# ESP12_BusinessCard.net
KiCad netlist of a schematic drawn in EAGLE
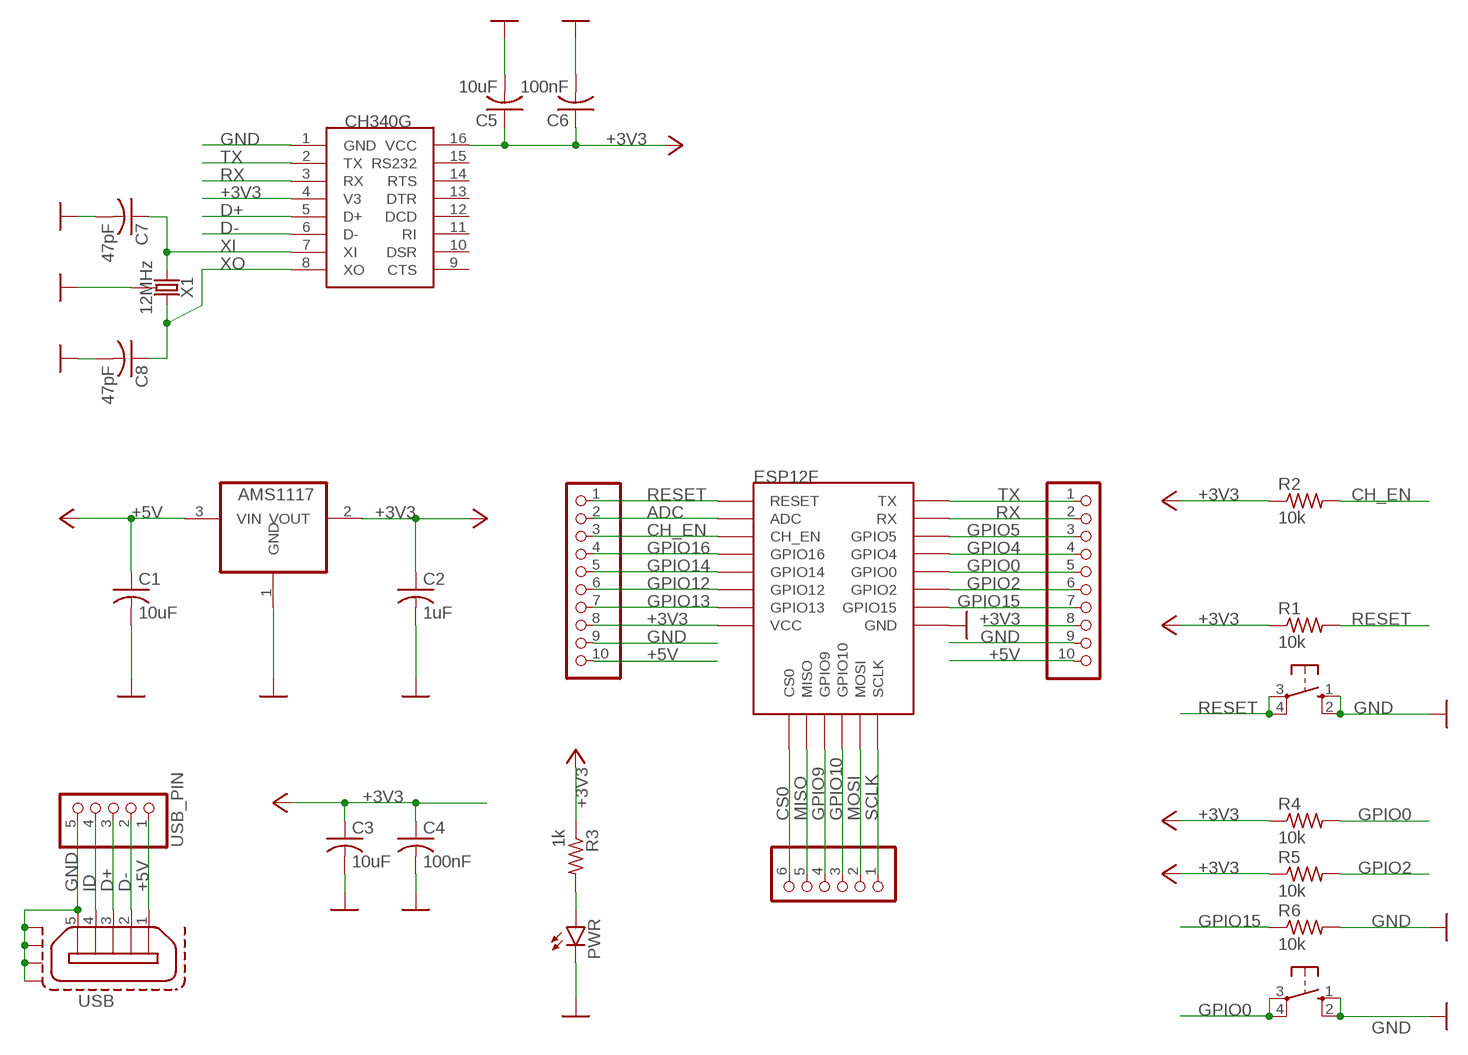
[diagram p0: schematic, sheet 1]

(export (version "E")
  (design (tool "Eeschema 10.0.6"))
  (components
    (comp (ref "AMS1117")
      (value "AMS1117")
      (footprint "eagle-import:SOT223")
      (fields (field (name "MPN") "REG1117"))
      (libsource (lib "eagle-import") (part "REG1117"))
    )
    (comp (ref "C1")
      (value "10uF")
      (footprint "eagle-import:C0805")
      (libsource (lib "eagle-import") (part "C-USC0805"))
    )
    (comp (ref "C2")
      (value "1uF")
      (footprint "eagle-import:C0805")
      (libsource (lib "eagle-import") (part "C-USC0805"))
    )
    (comp (ref "C3")
      (value "10uF")
      (footprint "eagle-import:C0805")
      (libsource (lib "eagle-import") (part "C-USC0805"))
    )
    (comp (ref "C4")
      (value "100nF")
      (footprint "eagle-import:C0805")
      (libsource (lib "eagle-import") (part "C-USC0805"))
    )
    (comp (ref "C5")
      (value "10uF")
      (footprint "eagle-import:C0805")
      (libsource (lib "eagle-import") (part "C-USC0805"))
    )
    (comp (ref "C6")
      (value "100nF")
      (footprint "eagle-import:C0805")
      (libsource (lib "eagle-import") (part "C-USC0805"))
    )
    (comp (ref "C7")
      (value "47pF")
      (footprint "eagle-import:C0805")
      (libsource (lib "eagle-import") (part "C-USC0805"))
    )
    (comp (ref "C8")
      (value "47pF")
      (footprint "eagle-import:C0805")
      (libsource (lib "eagle-import") (part "C-USC0805"))
    )
    (comp (ref "CH340G")
      (value "CH340G")
      (footprint "eagle-import:SOIC16")
      (libsource (lib "eagle-import") (part "CH340G"))
    )
    (comp (ref "ESP12F")
      (value "ESP12FSMD")
      (footprint "eagle-import:ESP12E-SMD")
      (libsource (lib "eagle-import") (part "ESP12FSMD"))
    )
    (comp (ref "JP1")
      (value "PINHD-1X10")
      (footprint "eagle-import:1X10")
      (libsource (lib "eagle-import") (part "PINHD-1X10"))
    )
    (comp (ref "JP2")
      (value "PINHD-1X10")
      (footprint "eagle-import:1X10")
      (libsource (lib "eagle-import") (part "PINHD-1X10"))
    )
    (comp (ref "JP3")
      (value "PINHD-1X6")
      (footprint "eagle-import:1X06")
      (libsource (lib "eagle-import") (part "PINHD-1X6"))
    )
    (comp (ref "PWR")
      (value "LEDCHIP-LED0603")
      (footprint "eagle-import:CHIP-LED0603")
      (libsource (lib "eagle-import") (part "LEDCHIP-LED0603"))
    )
    (comp (ref "R1")
      (value "10k")
      (footprint "eagle-import:R0805")
      (libsource (lib "eagle-import") (part "R-US_R0805"))
    )
    (comp (ref "R2")
      (value "10k")
      (footprint "eagle-import:R0805")
      (libsource (lib "eagle-import") (part "R-US_R0805"))
    )
    (comp (ref "R3")
      (value "1k")
      (footprint "eagle-import:R0805")
      (libsource (lib "eagle-import") (part "R-US_R0805"))
    )
    (comp (ref "R4")
      (value "10k")
      (footprint "eagle-import:R0805")
      (libsource (lib "eagle-import") (part "R-US_R0805"))
    )
    (comp (ref "R5")
      (value "10k")
      (footprint "eagle-import:R0805")
      (libsource (lib "eagle-import") (part "R-US_R0805"))
    )
    (comp (ref "R6")
      (value "10k")
      (footprint "eagle-import:R0805")
      (libsource (lib "eagle-import") (part "R-US_R0805"))
    )
    (comp (ref "S_PROG")
      (value "10-XX")
      (footprint "eagle-import:B3F-10XX")
      (fields (field (name "MPN") "B3F-1000"))
      (libsource (lib "eagle-import") (part "10-XX"))
    )
    (comp (ref "S_RESET")
      (value "10-XX")
      (footprint "eagle-import:B3F-10XX")
      (fields (field (name "MPN") "B3F-1000"))
      (libsource (lib "eagle-import") (part "10-XX"))
    )
    (comp (ref "USB")
      (value "ZX62D-B-5PA8")
      (footprint "eagle-import:ZX62D-B-5PA8")
      (fields (field (name "MF") "Hirose"))
      (libsource (lib "eagle-import") (part "ZX62D-B-5PA8"))
    )
    (comp (ref "USB_PIN")
      (value "PINHD-1X5")
      (footprint "eagle-import:1X05")
      (libsource (lib "eagle-import") (part "PINHD-1X5"))
    )
    (comp (ref "X1")
      (value "12MHz")
      (footprint "eagle-import:CRYSTAL-SMD-3.2X2.5MM")
      (libsource (lib "eagle-import") (part "CRYSTAL-GROUNDEDSMD-3.2X2.5"))
    )
  )
  (nets
    (net (code "1") (name "+3V3") (class "Default")
      (node (ref "AMS1117") (pin "2") (pinfunction "VOUT_2") (pintype "output"))
      (node (ref "C2") (pin "1") (pinfunction "1_1") (pintype "passive"))
      (node (ref "C3") (pin "1") (pinfunction "1_1") (pintype "passive"))
      (node (ref "C4") (pin "1") (pinfunction "1_1") (pintype "passive"))
      (node (ref "C5") (pin "1") (pinfunction "1_1") (pintype "passive"))
      (node (ref "C6") (pin "1") (pinfunction "1_1") (pintype "passive"))
      (node (ref "CH340G") (pin "16") (pinfunction "VCC_16") (pintype "bidirectional"))
      (node (ref "CH340G") (pin "4") (pinfunction "V3_4") (pintype "bidirectional"))
      (node (ref "ESP12F") (pin "VCC") (pinfunction "VCC_VCC") (pintype "bidirectional"))
      (node (ref "JP1") (pin "8") (pinfunction "8_8") (pintype "passive"))
      (node (ref "JP2") (pin "8") (pinfunction "8_8") (pintype "passive"))
      (node (ref "R1") (pin "1") (pinfunction "1_1") (pintype "passive"))
      (node (ref "R2") (pin "1") (pinfunction "1_1") (pintype "passive"))
      (node (ref "R3") (pin "1") (pinfunction "1_1") (pintype "passive"))
      (node (ref "R4") (pin "1") (pinfunction "1_1") (pintype "passive"))
      (node (ref "R5") (pin "1") (pinfunction "1_1") (pintype "passive"))
    )
    (net (code "2") (name "+5V") (class "Default")
      (node (ref "AMS1117") (pin "3") (pinfunction "VIN_3") (pintype "input"))
      (node (ref "C1") (pin "1") (pinfunction "1_1") (pintype "passive"))
      (node (ref "JP1") (pin "10") (pinfunction "10_10") (pintype "passive"))
      (node (ref "JP2") (pin "10") (pinfunction "10_10") (pintype "passive"))
      (node (ref "USB") (pin "1") (pinfunction "1_1") (pintype "passive"))
      (node (ref "USB_PIN") (pin "1") (pinfunction "1_1") (pintype "passive"))
    )
    (net (code "3") (name "/ADC") (class "Default")
      (node (ref "ESP12F") (pin "ADC") (pinfunction "ADC_ADC") (pintype "bidirectional"))
      (node (ref "JP1") (pin "2") (pinfunction "2_2") (pintype "passive"))
    )
    (net (code "4") (name "/CH_EN") (class "Default")
      (node (ref "ESP12F") (pin "CH_PD") (pinfunction "CH_EN_CH_PD") (pintype "bidirectional"))
      (node (ref "JP1") (pin "3") (pinfunction "3_3") (pintype "passive"))
      (node (ref "R2") (pin "2") (pinfunction "2_2") (pintype "passive"))
    )
    (net (code "5") (name "/CS0") (class "Default")
      (node (ref "ESP12F") (pin "CS0") (pinfunction "CS0_CS0") (pintype "bidirectional"))
      (node (ref "JP3") (pin "6") (pinfunction "6_6") (pintype "passive"))
    )
    (net (code "6") (name "/D+") (class "Default")
      (node (ref "CH340G") (pin "5") (pinfunction "D+_5") (pintype "bidirectional"))
      (node (ref "USB") (pin "3") (pinfunction "3_3") (pintype "passive"))
      (node (ref "USB_PIN") (pin "3") (pinfunction "3_3") (pintype "passive"))
    )
    (net (code "7") (name "/D-") (class "Default")
      (node (ref "CH340G") (pin "6") (pinfunction "D-_6") (pintype "bidirectional"))
      (node (ref "USB") (pin "2") (pinfunction "2_2") (pintype "passive"))
      (node (ref "USB_PIN") (pin "2") (pinfunction "2_2") (pintype "passive"))
    )
    (net (code "8") (name "/GPIO0") (class "Default")
      (node (ref "ESP12F") (pin "GPIO0") (pinfunction "GPIO0_GPIO0") (pintype "bidirectional"))
      (node (ref "JP2") (pin "5") (pinfunction "5_5") (pintype "passive"))
      (node (ref "R4") (pin "2") (pinfunction "2_2") (pintype "passive"))
      (node (ref "S_PROG") (pin "3") (pinfunction "P_3") (pintype "passive"))
      (node (ref "S_PROG") (pin "4") (pinfunction "P1_4") (pintype "passive"))
    )
    (net (code "9") (name "/GPIO2") (class "Default")
      (node (ref "ESP12F") (pin "GPIO2") (pinfunction "GPIO2_GPIO2") (pintype "bidirectional"))
      (node (ref "JP2") (pin "6") (pinfunction "6_6") (pintype "passive"))
      (node (ref "R5") (pin "2") (pinfunction "2_2") (pintype "passive"))
    )
    (net (code "10") (name "/GPIO4") (class "Default")
      (node (ref "ESP12F") (pin "GPIO4") (pinfunction "GPIO4_GPIO4") (pintype "bidirectional"))
      (node (ref "JP2") (pin "4") (pinfunction "4_4") (pintype "passive"))
    )
    (net (code "11") (name "/GPIO5") (class "Default")
      (node (ref "ESP12F") (pin "GPIO5") (pinfunction "GPIO5_GPIO5") (pintype "bidirectional"))
      (node (ref "JP2") (pin "3") (pinfunction "3_3") (pintype "passive"))
    )
    (net (code "12") (name "/GPIO9") (class "Default")
      (node (ref "ESP12F") (pin "GPIO9") (pinfunction "GPIO9_GPIO9") (pintype "bidirectional"))
      (node (ref "JP3") (pin "4") (pinfunction "4_4") (pintype "passive"))
    )
    (net (code "13") (name "/GPIO10") (class "Default")
      (node (ref "ESP12F") (pin "GPIO10") (pinfunction "GPIO10_GPIO10") (pintype "bidirectional"))
      (node (ref "JP3") (pin "3") (pinfunction "3_3") (pintype "passive"))
    )
    (net (code "14") (name "/GPIO12") (class "Default")
      (node (ref "ESP12F") (pin "GPIO12") (pinfunction "GPIO12_GPIO12") (pintype "bidirectional"))
      (node (ref "JP1") (pin "6") (pinfunction "6_6") (pintype "passive"))
    )
    (net (code "15") (name "/GPIO13") (class "Default")
      (node (ref "ESP12F") (pin "GPIO13") (pinfunction "GPIO13_GPIO13") (pintype "bidirectional"))
      (node (ref "JP1") (pin "7") (pinfunction "7_7") (pintype "passive"))
    )
    (net (code "16") (name "/GPIO14") (class "Default")
      (node (ref "ESP12F") (pin "GPIO14") (pinfunction "GPIO14_GPIO14") (pintype "bidirectional"))
      (node (ref "JP1") (pin "5") (pinfunction "5_5") (pintype "passive"))
    )
    (net (code "17") (name "/GPIO15") (class "Default")
      (node (ref "ESP12F") (pin "GPIO15") (pinfunction "GPIO15_GPIO15") (pintype "bidirectional"))
      (node (ref "JP2") (pin "7") (pinfunction "7_7") (pintype "passive"))
      (node (ref "R6") (pin "1") (pinfunction "1_1") (pintype "passive"))
    )
    (net (code "18") (name "/GPIO16") (class "Default")
      (node (ref "ESP12F") (pin "GPIO16") (pinfunction "GPIO16_GPIO16") (pintype "bidirectional"))
      (node (ref "JP1") (pin "4") (pinfunction "4_4") (pintype "passive"))
    )
    (net (code "19") (name "/ID") (class "Default")
      (node (ref "USB") (pin "4") (pinfunction "4_4") (pintype "passive"))
      (node (ref "USB_PIN") (pin "4") (pinfunction "4_4") (pintype "passive"))
    )
    (net (code "20") (name "/MISO") (class "Default")
      (node (ref "ESP12F") (pin "MISO") (pinfunction "MISO_MISO") (pintype "bidirectional"))
      (node (ref "JP3") (pin "5") (pinfunction "5_5") (pintype "passive"))
    )
    (net (code "21") (name "/MOSI") (class "Default")
      (node (ref "ESP12F") (pin "MOSI") (pinfunction "MOSI_MOSI") (pintype "bidirectional"))
      (node (ref "JP3") (pin "2") (pinfunction "2_2") (pintype "passive"))
    )
    (net (code "22") (name "/RESET") (class "Default")
      (node (ref "ESP12F") (pin "RESET") (pinfunction "RESET_RESET") (pintype "bidirectional"))
      (node (ref "JP1") (pin "1") (pinfunction "1_1") (pintype "passive"))
      (node (ref "R1") (pin "2") (pinfunction "2_2") (pintype "passive"))
      (node (ref "S_RESET") (pin "3") (pinfunction "P_3") (pintype "passive"))
      (node (ref "S_RESET") (pin "4") (pinfunction "P1_4") (pintype "passive"))
    )
    (net (code "23") (name "/RX") (class "Default")
      (node (ref "CH340G") (pin "3") (pinfunction "RX_3") (pintype "bidirectional"))
      (node (ref "ESP12F") (pin "RXD0") (pinfunction "RX_RXD0") (pintype "bidirectional"))
      (node (ref "JP2") (pin "2") (pinfunction "2_2") (pintype "passive"))
    )
    (net (code "24") (name "/SCLK") (class "Default")
      (node (ref "ESP12F") (pin "SCLK") (pinfunction "SCLK_SCLK") (pintype "bidirectional"))
      (node (ref "JP3") (pin "1") (pinfunction "1_1") (pintype "passive"))
    )
    (net (code "25") (name "/TX") (class "Default")
      (node (ref "CH340G") (pin "2") (pinfunction "TX_2") (pintype "bidirectional"))
      (node (ref "ESP12F") (pin "TXD0") (pinfunction "TX_TXD0") (pintype "bidirectional"))
      (node (ref "JP2") (pin "1") (pinfunction "1_1") (pintype "passive"))
    )
    (net (code "26") (name "/XI") (class "Default")
      (node (ref "C7") (pin "1") (pinfunction "1_1") (pintype "passive"))
      (node (ref "CH340G") (pin "7") (pinfunction "XI_7") (pintype "bidirectional"))
      (node (ref "X1") (pin "1") (pinfunction "1_1") (pintype "passive"))
    )
    (net (code "27") (name "/XO") (class "Default")
      (node (ref "C8") (pin "1") (pinfunction "1_1") (pintype "passive"))
      (node (ref "CH340G") (pin "8") (pinfunction "XO_8") (pintype "bidirectional"))
      (node (ref "X1") (pin "3") (pinfunction "2_3") (pintype "passive"))
    )
    (net (code "28") (name "GND") (class "Default")
      (node (ref "AMS1117") (pin "1") (pinfunction "GND_1") (pintype "power_in"))
      (node (ref "C1") (pin "2") (pinfunction "2_2") (pintype "passive"))
      (node (ref "C2") (pin "2") (pinfunction "2_2") (pintype "passive"))
      (node (ref "C3") (pin "2") (pinfunction "2_2") (pintype "passive"))
      (node (ref "C4") (pin "2") (pinfunction "2_2") (pintype "passive"))
      (node (ref "C5") (pin "2") (pinfunction "2_2") (pintype "passive"))
      (node (ref "C6") (pin "2") (pinfunction "2_2") (pintype "passive"))
      (node (ref "C7") (pin "2") (pinfunction "2_2") (pintype "passive"))
      (node (ref "C8") (pin "2") (pinfunction "2_2") (pintype "passive"))
      (node (ref "CH340G") (pin "1") (pinfunction "GND_1") (pintype "bidirectional"))
      (node (ref "ESP12F") (pin "GND") (pinfunction "GND_GND") (pintype "bidirectional"))
      (node (ref "JP1") (pin "9") (pinfunction "9_9") (pintype "passive"))
      (node (ref "JP2") (pin "9") (pinfunction "9_9") (pintype "passive"))
      (node (ref "PWR") (pin "C") (pinfunction "C_C") (pintype "passive"))
      (node (ref "R6") (pin "2") (pinfunction "2_2") (pintype "passive"))
      (node (ref "S_PROG") (pin "1") (pinfunction "S_1") (pintype "passive"))
      (node (ref "S_PROG") (pin "2") (pinfunction "S1_2") (pintype "passive"))
      (node (ref "S_RESET") (pin "1") (pinfunction "S_1") (pintype "passive"))
      (node (ref "S_RESET") (pin "2") (pinfunction "S1_2") (pintype "passive"))
      (node (ref "USB") (pin "5") (pinfunction "5_5") (pintype "passive"))
      (node (ref "USB") (pin "S1") (pinfunction "S1_S1") (pintype "passive"))
      (node (ref "USB") (pin "S2") (pinfunction "S2_S2") (pintype "passive"))
      (node (ref "USB") (pin "S3") (pinfunction "S3_S3") (pintype "passive"))
      (node (ref "USB") (pin "S4") (pinfunction "S4_S4") (pintype "passive"))
      (node (ref "USB_PIN") (pin "5") (pinfunction "5_5") (pintype "passive"))
      (node (ref "X1") (pin "2") (pinfunction "3_2") (pintype "passive"))
      (node (ref "X1") (pin "4") (pinfunction "3_4") (pintype "passive"))
    )
    (net (code "29") (name "Net-(PWR-PadA)") (class "Default")
      (node (ref "PWR") (pin "A") (pinfunction "A_A") (pintype "passive"))
      (node (ref "R3") (pin "2") (pinfunction "2_2") (pintype "passive"))
    )
    (net (code "30") (name "unconnected-(CH340G-CTS-Pad9)") (class "Default")
      (node (ref "CH340G") (pin "9") (pinfunction "CTS_9") (pintype "bidirectional"))
    )
    (net (code "31") (name "unconnected-(CH340G-DCD-Pad12)") (class "Default")
      (node (ref "CH340G") (pin "12") (pinfunction "DCD_12") (pintype "bidirectional"))
    )
    (net (code "32") (name "unconnected-(CH340G-DSR-Pad10)") (class "Default")
      (node (ref "CH340G") (pin "10") (pinfunction "DSR_10") (pintype "bidirectional"))
    )
    (net (code "33") (name "unconnected-(CH340G-DTR-Pad13)") (class "Default")
      (node (ref "CH340G") (pin "13") (pinfunction "DTR_13") (pintype "bidirectional"))
    )
    (net (code "34") (name "unconnected-(CH340G-RI-Pad11)") (class "Default")
      (node (ref "CH340G") (pin "11") (pinfunction "RI_11") (pintype "bidirectional"))
    )
    (net (code "35") (name "unconnected-(CH340G-RS232-Pad15)") (class "Default")
      (node (ref "CH340G") (pin "15") (pinfunction "RS232_15") (pintype "bidirectional"))
    )
    (net (code "36") (name "unconnected-(CH340G-RTS-Pad14)") (class "Default")
      (node (ref "CH340G") (pin "14") (pinfunction "RTS_14") (pintype "bidirectional"))
    )
  )
)
